# Actuator.net
KiCad netlist of a schematic drawn in EAGLE
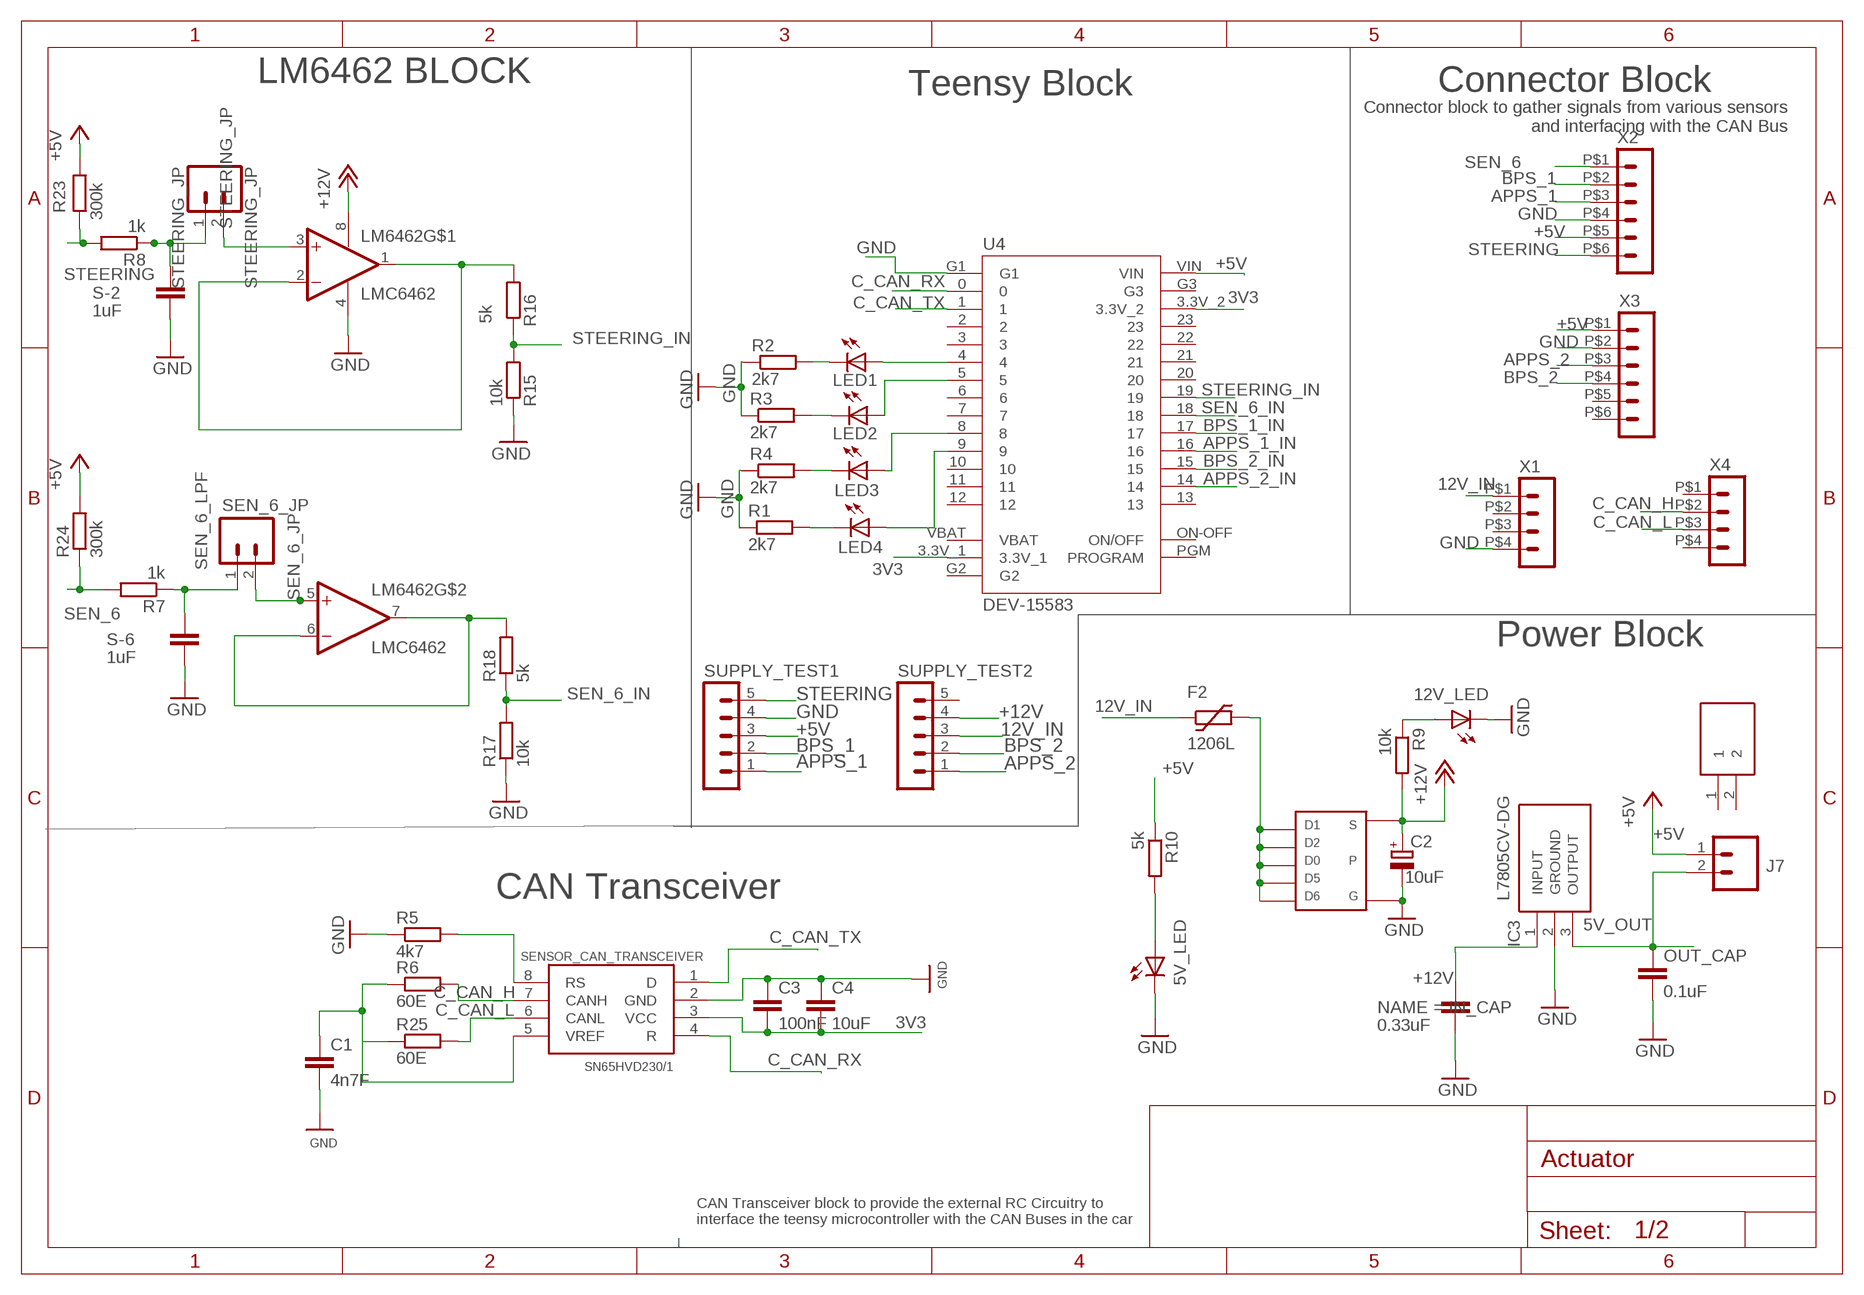
[diagram p0: schematic, sheet 1]
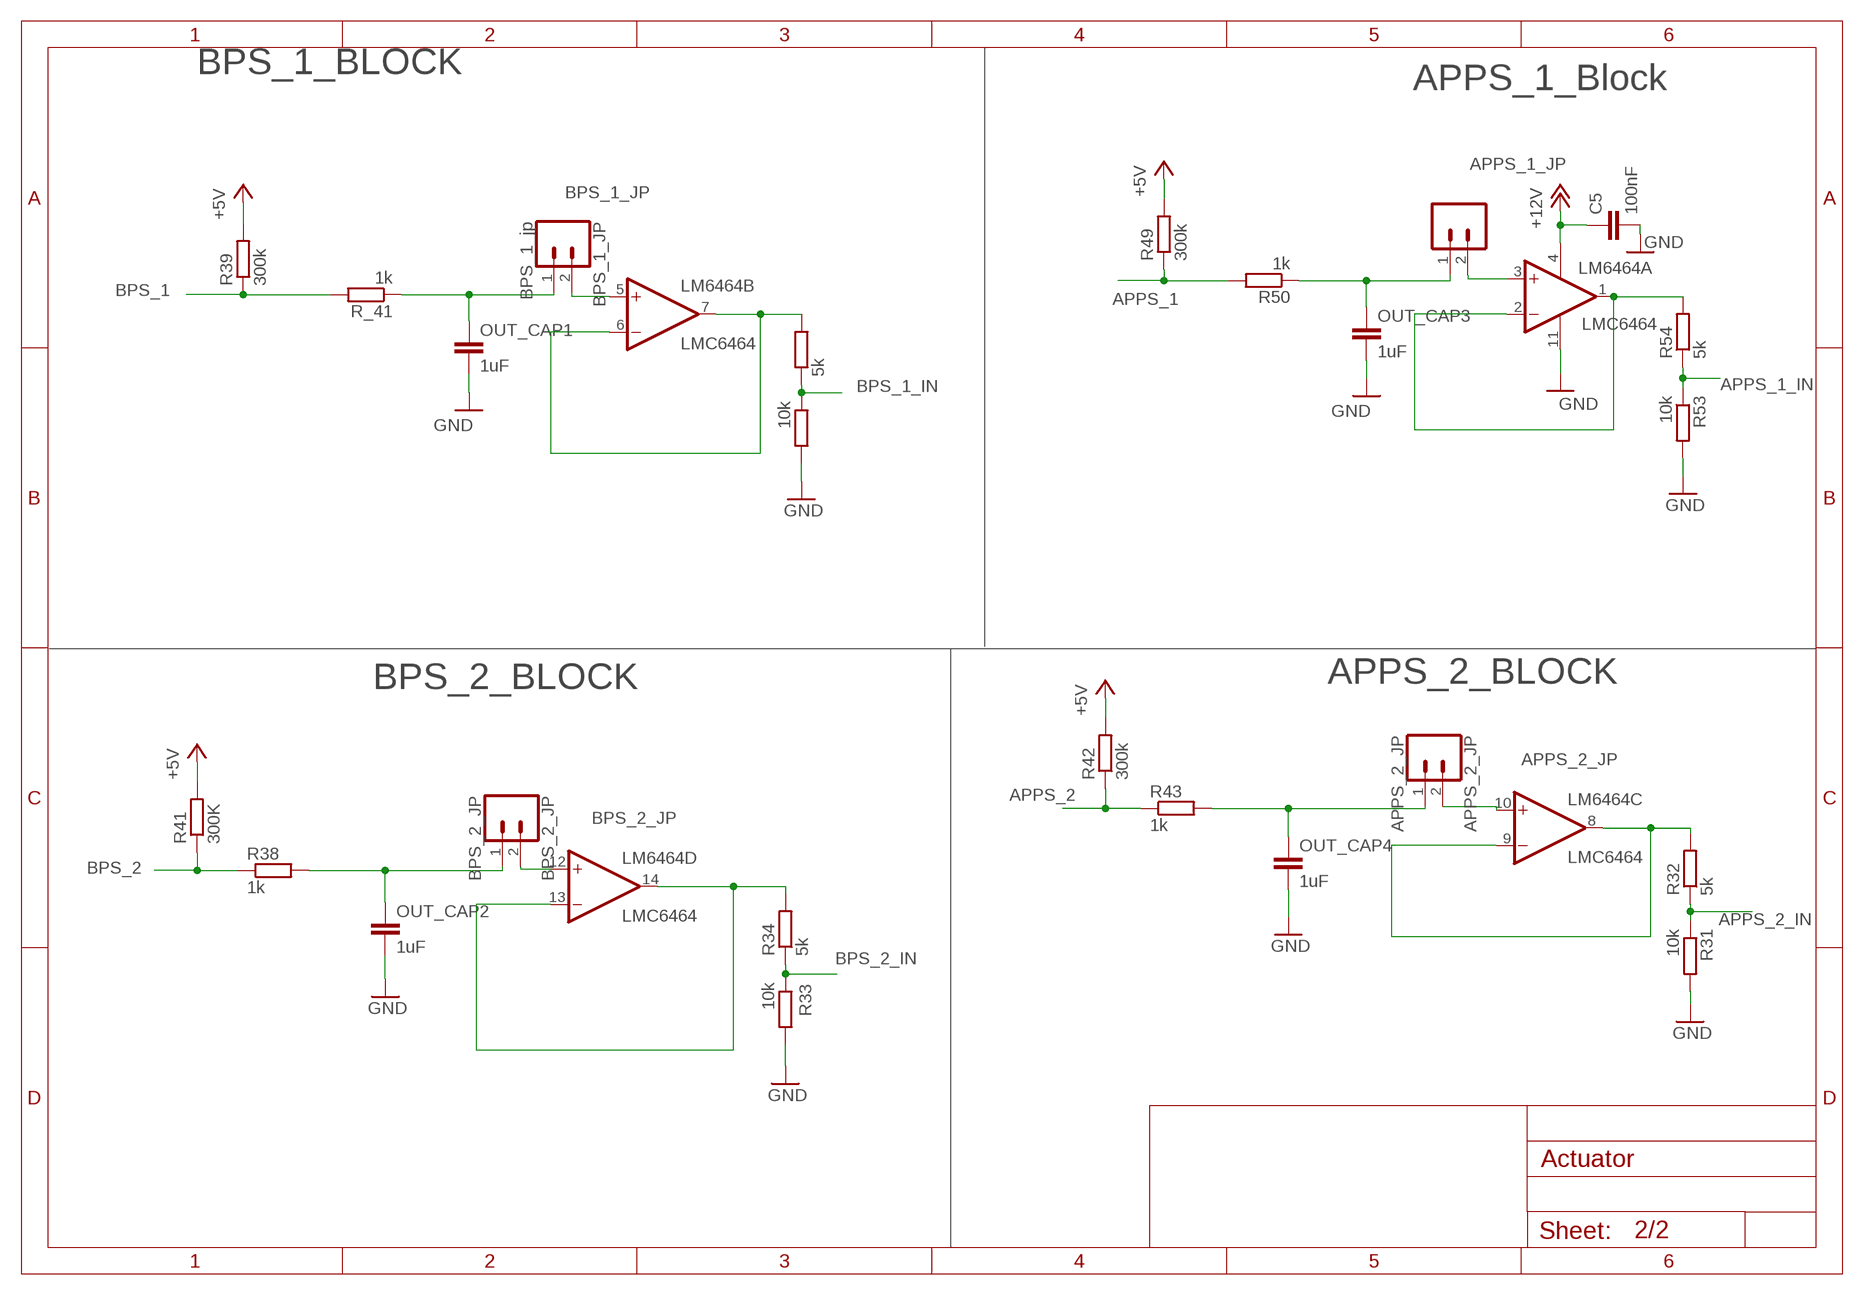
[diagram p1: schematic, sheet 2]

(export (version "E")
  (design (tool "Eeschema 10.0.6"))
  (components
    (comp (ref "5V_LED")
      (value "LED1206")
      (footprint "eagle-import:LED-1206")
      (libsource (lib "eagle-import") (part "LED1206"))
    )
    (comp (ref "12V_LED")
      (value "LED1206")
      (footprint "eagle-import:LED-1206")
      (libsource (lib "eagle-import") (part "LED1206"))
    )
    (comp (ref "C1")
      (value "4n7F")
      (footprint "eagle-import:C0805")
      (libsource (lib "eagle-import") (part "C-EUC0805"))
    )
    (comp (ref "C2")
      (value "10uF")
      (footprint "eagle-import:E2,5-6")
      (libsource (lib "eagle-import") (part "CPOL-EUE2.5-6"))
    )
    (comp (ref "C3")
      (value "100nF")
      (footprint "eagle-import:C0805")
      (libsource (lib "eagle-import") (part "C-EUC0805"))
    )
    (comp (ref "C4")
      (value "10uF")
      (footprint "eagle-import:C0805")
      (libsource (lib "eagle-import") (part "C-EUC0805"))
    )
    (comp (ref "F2")
      (value "1206L")
      (footprint "eagle-import:1206L")
      (libsource (lib "eagle-import") (part "1206L"))
    )
    (comp (ref "IC3")
      (value "L7805CV-DG")
      (footprint "eagle-import:TO255P460X1020X2008-3P")
      (fields (field (name "MOUSER_PART_NUMBER") "511-L7805CV-DG"))
      (libsource (lib "eagle-import") (part "L7805CV-DG"))
    )
    (comp (ref "IN_CAP")
      (value "0.33uF")
      (footprint "eagle-import:C0805")
      (libsource (lib "eagle-import") (part "C-EUC0805"))
    )
    (comp (ref "J7")
      (value "CONN_02")
      (footprint "eagle-import:1X02")
      (libsource (lib "eagle-import") (part "SparkFun-Connectors_CONN_02"))
    )
    (comp (ref "LED1")
      (value "LED1206")
      (footprint "eagle-import:LED-1206")
      (libsource (lib "eagle-import") (part "LED1206"))
    )
    (comp (ref "LED2")
      (value "LED1206")
      (footprint "eagle-import:LED-1206")
      (libsource (lib "eagle-import") (part "LED1206"))
    )
    (comp (ref "LED3")
      (value "LED1206")
      (footprint "eagle-import:LED-1206")
      (libsource (lib "eagle-import") (part "LED1206"))
    )
    (comp (ref "LED4")
      (value "LED1206")
      (footprint "eagle-import:LED-1206")
      (libsource (lib "eagle-import") (part "LED1206"))
    )
    (comp (ref "LM6462")
      (value "LMC6462")
      (footprint "eagle-import:S08")
      (libsource (lib "eagle-import") (part "LMC6462"))
    )
    (comp (ref "OUT_CAP")
      (value "0.1uF")
      (footprint "eagle-import:C0805")
      (libsource (lib "eagle-import") (part "C-EUC0805"))
    )
    (comp (ref "R1")
      (value "2k7")
      (footprint "eagle-import:R0805")
      (libsource (lib "eagle-import") (part "rcl_R-EU_R0805"))
    )
    (comp (ref "R2")
      (value "2k7")
      (footprint "eagle-import:R0805")
      (libsource (lib "eagle-import") (part "rcl_R-EU_R0805"))
    )
    (comp (ref "R3")
      (value "2k7")
      (footprint "eagle-import:R0805")
      (libsource (lib "eagle-import") (part "rcl_R-EU_R0805"))
    )
    (comp (ref "R4")
      (value "2k7")
      (footprint "eagle-import:R0805")
      (libsource (lib "eagle-import") (part "rcl_R-EU_R0805"))
    )
    (comp (ref "R5")
      (value "4k7")
      (footprint "eagle-import:R0805")
      (libsource (lib "eagle-import") (part "R-EU_R0805"))
    )
    (comp (ref "R6")
      (value "60E")
      (footprint "eagle-import:R0805")
      (libsource (lib "eagle-import") (part "R-EU_R0805"))
    )
    (comp (ref "R7")
      (value "1k")
      (footprint "eagle-import:R0805")
      (libsource (lib "eagle-import") (part "IIT_BOMBAY_Racing2_R-EU_R0805"))
    )
    (comp (ref "R8")
      (value "1k")
      (footprint "eagle-import:R0805")
      (libsource (lib "eagle-import") (part "IIT_BOMBAY_Racing2_R-EU_R0805"))
    )
    (comp (ref "R9")
      (value "10k")
      (footprint "eagle-import:R0805")
      (libsource (lib "eagle-import") (part "R-EU_R0805"))
    )
    (comp (ref "R10")
      (value "5k")
      (footprint "eagle-import:R0805")
      (libsource (lib "eagle-import") (part "R-EU_R0805"))
    )
    (comp (ref "R15")
      (value "10k")
      (footprint "eagle-import:R0805")
      (libsource (lib "eagle-import") (part "IIT_BOMBAY_Racing2_R-EU_R0805"))
    )
    (comp (ref "R16")
      (value "5k")
      (footprint "eagle-import:R0805")
      (libsource (lib "eagle-import") (part "IIT_BOMBAY_Racing2_R-EU_R0805"))
    )
    (comp (ref "R17")
      (value "10k")
      (footprint "eagle-import:R0805")
      (libsource (lib "eagle-import") (part "IIT_BOMBAY_Racing2_R-EU_R0805"))
    )
    (comp (ref "R18")
      (value "5k")
      (footprint "eagle-import:R0805")
      (libsource (lib "eagle-import") (part "IIT_BOMBAY_Racing2_R-EU_R0805"))
    )
    (comp (ref "R23")
      (value "300k")
      (footprint "eagle-import:R0805")
      (libsource (lib "eagle-import") (part "IIT_BOMBAY_Racing2_R-EU_R0805"))
    )
    (comp (ref "R24")
      (value "300k")
      (footprint "eagle-import:R0805")
      (libsource (lib "eagle-import") (part "IIT_BOMBAY_Racing2_R-EU_R0805"))
    )
    (comp (ref "R25")
      (value "60E")
      (footprint "eagle-import:R0805")
      (libsource (lib "eagle-import") (part "R-EU_R0805"))
    )
    (comp (ref "S-2")
      (value "1uF")
      (footprint "eagle-import:C0805")
      (libsource (lib "eagle-import") (part "C-EUC0805"))
    )
    (comp (ref "S-6")
      (value "1uF")
      (footprint "eagle-import:C0805")
      (libsource (lib "eagle-import") (part "C-EUC0805"))
    )
    (comp (ref "SENSOR_CAN_TRANSCEIVER")
      (value "SN65HVD230/1")
      (footprint "eagle-import:SO8")
      (libsource (lib "eagle-import") (part "SN65HVD230/1"))
    )
    (comp (ref "SEN_6_JP")
      (value "SEN_6_JP")
      (footprint "eagle-import:1X02")
      (libsource (lib "eagle-import") (part "CONN_02"))
    )
    (comp (ref "STEERING_JP")
      (value "STEERING_JP")
      (footprint "eagle-import:1X02")
      (libsource (lib "eagle-import") (part "CONN_02"))
    )
    (comp (ref "SUPPLY_TEST1")
      (value "MA05-1")
      (footprint "eagle-import:MA05-1")
      (libsource (lib "eagle-import") (part "MA05-1"))
    )
    (comp (ref "SUPPLY_TEST2")
      (value "MA05-1")
      (footprint "eagle-import:MA05-1")
      (libsource (lib "eagle-import") (part "MA05-1"))
    )
    (comp (ref "U$1")
      (value "TSOP-6_PMOS")
      (footprint "eagle-import:TSOP-6_PMOS")
      (libsource (lib "eagle-import") (part "TSOP-6_PMOS"))
    )
    (comp (ref "U3")
      (value "HSS10-B20-P40")
      (footprint "eagle-import:HSS10B20P40")
      (fields (field (name "MOUSER_PART_NUMBER") "490-HSS10-B20-P40"))
      (libsource (lib "eagle-import") (part "HSS10-B20-P40"))
    )
    (comp (ref "U4")
      (value "DEV-15583")
      (footprint "eagle-import:MODULE_DEV-15583")
      (fields (field (name "MF") "SparkFun Electronics"))
      (libsource (lib "eagle-import") (part "DEV-15583"))
    )
    (comp (ref "X1")
      (value "HEADER_POS4_43045-0412")
      (footprint "eagle-import:43045-0412")
      (libsource (lib "eagle-import") (part "HEADER_POS4_?43045-0412"))
    )
    (comp (ref "X2")
      (value "HEADER_POS6_43045-0612")
      (footprint "eagle-import:43045-0612")
      (libsource (lib "eagle-import") (part "HEADER_POS6_?43045-0612"))
    )
    (comp (ref "X3")
      (value "HEADER_POS6_43045-0612")
      (footprint "eagle-import:43045-0612")
      (libsource (lib "eagle-import") (part "HEADER_POS6_?43045-0612"))
    )
    (comp (ref "X4")
      (value "HEADER_POS4_43045-0412")
      (footprint "eagle-import:43045-0412")
      (libsource (lib "eagle-import") (part "HEADER_POS4_?43045-0412"))
    )
    (comp (ref "APPS_1_JP")
      (value "CONN_02")
      (footprint "eagle-import:1X02")
      (libsource (lib "eagle-import") (part "CONN_02"))
    )
    (comp (ref "APPS_2_JP")
      (value "APPS_2_JP")
      (footprint "eagle-import:1X02")
      (libsource (lib "eagle-import") (part "CONN_02"))
    )
    (comp (ref "BPS_1_JP")
      (value "BPS_1_jp")
      (footprint "eagle-import:1X02")
      (libsource (lib "eagle-import") (part "CONN_02"))
    )
    (comp (ref "BPS_2_JP")
      (value "BPS_2_JP")
      (footprint "eagle-import:1X02")
      (libsource (lib "eagle-import") (part "CONN_02"))
    )
    (comp (ref "C5")
      (value "100nF")
      (footprint "eagle-import:C0805")
      (libsource (lib "eagle-import") (part "C-EUC0805"))
    )
    (comp (ref "LM6464")
      (value "LMC6464")
      (footprint "eagle-import:SO14_LONGPADS")
      (libsource (lib "eagle-import") (part "LMC6464"))
    )
    (comp (ref "OUT_CAP1")
      (value "1uF")
      (footprint "eagle-import:C0805")
      (libsource (lib "eagle-import") (part "C-EUC0805"))
    )
    (comp (ref "OUT_CAP2")
      (value "1uF")
      (footprint "eagle-import:C0805")
      (libsource (lib "eagle-import") (part "C-EUC0805"))
    )
    (comp (ref "OUT_CAP3")
      (value "1uF")
      (footprint "eagle-import:C0805")
      (libsource (lib "eagle-import") (part "C-EUC0805"))
    )
    (comp (ref "OUT_CAP4")
      (value "1uF")
      (footprint "eagle-import:C0805")
      (libsource (lib "eagle-import") (part "C-EUC0805"))
    )
    (comp (ref "R29")
      (value "10k")
      (footprint "eagle-import:R0805")
      (libsource (lib "eagle-import") (part "IIT_BOMBAY_Racing2_R-EU_R0805"))
    )
    (comp (ref "R30")
      (value "5k")
      (footprint "eagle-import:R0805")
      (libsource (lib "eagle-import") (part "IIT_BOMBAY_Racing2_R-EU_R0805"))
    )
    (comp (ref "R31")
      (value "10k")
      (footprint "eagle-import:R0805")
      (libsource (lib "eagle-import") (part "IIT_BOMBAY_Racing2_R-EU_R0805"))
    )
    (comp (ref "R32")
      (value "5k")
      (footprint "eagle-import:R0805")
      (libsource (lib "eagle-import") (part "IIT_BOMBAY_Racing2_R-EU_R0805"))
    )
    (comp (ref "R33")
      (value "10k")
      (footprint "eagle-import:R0805")
      (libsource (lib "eagle-import") (part "IIT_BOMBAY_Racing2_R-EU_R0805"))
    )
    (comp (ref "R34")
      (value "5k")
      (footprint "eagle-import:R0805")
      (libsource (lib "eagle-import") (part "IIT_BOMBAY_Racing2_R-EU_R0805"))
    )
    (comp (ref "R38")
      (value "1k")
      (footprint "eagle-import:R0805")
      (libsource (lib "eagle-import") (part "IIT_BOMBAY_Racing2_R-EU_R0805"))
    )
    (comp (ref "R39")
      (value "300k")
      (footprint "eagle-import:R0805")
      (libsource (lib "eagle-import") (part "IIT_BOMBAY_Racing2_R-EU_R0805"))
    )
    (comp (ref "R41")
      (value "300K")
      (footprint "eagle-import:R0805")
      (libsource (lib "eagle-import") (part "IIT_BOMBAY_Racing2_R-EU_R0805"))
    )
    (comp (ref "R42")
      (value "300k")
      (footprint "eagle-import:R0805")
      (libsource (lib "eagle-import") (part "IIT_BOMBAY_Racing2_R-EU_R0805"))
    )
    (comp (ref "R43")
      (value "1k")
      (footprint "eagle-import:R0805")
      (libsource (lib "eagle-import") (part "IIT_BOMBAY_Racing2_R-EU_R0805"))
    )
    (comp (ref "R49")
      (value "300k")
      (footprint "eagle-import:R0805")
      (libsource (lib "eagle-import") (part "IIT_BOMBAY_Racing2_R-EU_R0805"))
    )
    (comp (ref "R50")
      (value "1k")
      (footprint "eagle-import:R0805")
      (libsource (lib "eagle-import") (part "IIT_BOMBAY_Racing2_R-EU_R0805"))
    )
    (comp (ref "R53")
      (value "10k")
      (footprint "eagle-import:R0805")
      (libsource (lib "eagle-import") (part "IIT_BOMBAY_Racing2_R-EU_R0805"))
    )
    (comp (ref "R54")
      (value "5k")
      (footprint "eagle-import:R0805")
      (libsource (lib "eagle-import") (part "IIT_BOMBAY_Racing2_R-EU_R0805"))
    )
    (comp (ref "R_41")
      (value "1k")
      (footprint "eagle-import:R0805")
      (libsource (lib "eagle-import") (part "IIT_BOMBAY_Racing2_R-EU_R0805"))
    )
  )
  (nets
    (net (code "1") (name "+5V") (class "Default")
      (node (ref "J7") (pin "1") (pinfunction "1_1") (pintype "passive"))
      (node (ref "R10") (pin "1") (pinfunction "1_1") (pintype "passive"))
      (node (ref "R23") (pin "2") (pinfunction "2_2") (pintype "passive"))
      (node (ref "R24") (pin "2") (pinfunction "2_2") (pintype "passive"))
      (node (ref "R39") (pin "2") (pinfunction "2_2") (pintype "passive"))
      (node (ref "R41") (pin "2") (pinfunction "2_2") (pintype "passive"))
      (node (ref "R42") (pin "2") (pinfunction "2_2") (pintype "passive"))
      (node (ref "R49") (pin "2") (pinfunction "2_2") (pintype "passive"))
      (node (ref "SUPPLY_TEST1") (pin "3") (pinfunction "3_3") (pintype "passive"))
      (node (ref "U4") (pin "VIN") (pinfunction "VIN_VIN") (pintype "power_in"))
      (node (ref "X2") (pin "P$5") (pinfunction "5_P$5") (pintype "passive"))
      (node (ref "X3") (pin "P$1") (pinfunction "1_P$1") (pintype "passive"))
    )
    (net (code "2") (name "+12V") (class "Default")
      (node (ref "C2") (pin "+") (pinfunction "+_+") (pintype "passive"))
      (node (ref "C5") (pin "1") (pinfunction "1_1") (pintype "passive"))
      (node (ref "IC3") (pin "1") (pinfunction "INPUT_1") (pintype "bidirectional"))
      (node (ref "IN_CAP") (pin "1") (pinfunction "1_1") (pintype "passive"))
      (node (ref "LM6462") (pin "8") (pinfunction "V+_8") (pintype "power_in"))
      (node (ref "LM6464") (pin "4") (pinfunction "V+_4") (pintype "power_in"))
      (node (ref "R9") (pin "2") (pinfunction "2_2") (pintype "passive"))
      (node (ref "SUPPLY_TEST2") (pin "4") (pinfunction "4_4") (pintype "passive"))
      (node (ref "U$1") (pin "S") (pinfunction "S_S") (pintype "bidirectional"))
    )
    (net (code "3") (name "3V3") (class "Default")
      (node (ref "C3") (pin "2") (pinfunction "2_2") (pintype "passive"))
      (node (ref "C4") (pin "2") (pinfunction "2_2") (pintype "passive"))
      (node (ref "SENSOR_CAN_TRANSCEIVER") (pin "3") (pinfunction "VCC_3") (pintype "power_in"))
      (node (ref "U4") (pin "3.3V_1") (pinfunction "3.3V_1_3.3V_1") (pintype "power_in"))
      (node (ref "U4") (pin "3.3V_2") (pinfunction "3.3V_2_3.3V_2") (pintype "power_in"))
    )
    (net (code "4") (name "5V_OUT") (class "Default")
      (node (ref "IC3") (pin "3") (pinfunction "OUTPUT_3") (pintype "bidirectional"))
      (node (ref "J7") (pin "2") (pinfunction "2_2") (pintype "passive"))
      (node (ref "OUT_CAP") (pin "1") (pinfunction "1_1") (pintype "passive"))
    )
    (net (code "5") (name "12V_IN") (class "Default")
      (node (ref "F2") (pin "P$1") (pinfunction "1_P$1") (pintype "passive"))
      (node (ref "SUPPLY_TEST2") (pin "3") (pinfunction "3_3") (pintype "passive"))
      (node (ref "X1") (pin "P$1") (pinfunction "1_P$1") (pintype "passive"))
    )
    (net (code "6") (name "APPS_1") (class "Default")
      (node (ref "R49") (pin "1") (pinfunction "1_1") (pintype "passive"))
      (node (ref "R50") (pin "2") (pinfunction "2_2") (pintype "passive"))
      (node (ref "SUPPLY_TEST1") (pin "1") (pinfunction "1_1") (pintype "passive"))
      (node (ref "X2") (pin "P$3") (pinfunction "3_P$3") (pintype "passive"))
    )
    (net (code "7") (name "APPS_1_IN") (class "Default")
      (node (ref "R53") (pin "1") (pinfunction "1_1") (pintype "passive"))
      (node (ref "R54") (pin "1") (pinfunction "1_1") (pintype "passive"))
      (node (ref "U4") (pin "16") (pinfunction "16_16") (pintype "bidirectional"))
    )
    (net (code "8") (name "APPS_1_JP") (class "Default")
      (node (ref "APPS_1_JP") (pin "2") (pinfunction "2_2") (pintype "passive"))
      (node (ref "LM6464") (pin "3") (pinfunction "+IN_3") (pintype "input"))
    )
    (net (code "9") (name "APPS_2") (class "Default")
      (node (ref "R42") (pin "1") (pinfunction "1_1") (pintype "passive"))
      (node (ref "R43") (pin "1") (pinfunction "1_1") (pintype "passive"))
      (node (ref "SUPPLY_TEST2") (pin "1") (pinfunction "1_1") (pintype "passive"))
      (node (ref "X3") (pin "P$3") (pinfunction "3_P$3") (pintype "passive"))
    )
    (net (code "10") (name "APPS_2_IN") (class "Default")
      (node (ref "R31") (pin "1") (pinfunction "1_1") (pintype "passive"))
      (node (ref "R32") (pin "1") (pinfunction "1_1") (pintype "passive"))
      (node (ref "U4") (pin "14") (pinfunction "14_14") (pintype "bidirectional"))
    )
    (net (code "11") (name "APPS_2_JP") (class "Default")
      (node (ref "APPS_2_JP") (pin "2") (pinfunction "2_2") (pintype "passive"))
      (node (ref "LM6464") (pin "10") (pinfunction "+IN_10") (pintype "input"))
    )
    (net (code "12") (name "BPS_1") (class "Default")
      (node (ref "R39") (pin "1") (pinfunction "1_1") (pintype "passive"))
      (node (ref "R_41") (pin "2") (pinfunction "2_2") (pintype "passive"))
      (node (ref "SUPPLY_TEST1") (pin "2") (pinfunction "2_2") (pintype "passive"))
      (node (ref "X2") (pin "P$2") (pinfunction "2_P$2") (pintype "passive"))
    )
    (net (code "13") (name "BPS_1_IN") (class "Default")
      (node (ref "R29") (pin "1") (pinfunction "1_1") (pintype "passive"))
      (node (ref "R30") (pin "1") (pinfunction "1_1") (pintype "passive"))
      (node (ref "U4") (pin "17") (pinfunction "17_17") (pintype "bidirectional"))
    )
    (net (code "14") (name "BPS_1_JP") (class "Default")
      (node (ref "BPS_1_JP") (pin "2") (pinfunction "2_2") (pintype "passive"))
      (node (ref "LM6464") (pin "5") (pinfunction "+IN_5") (pintype "input"))
    )
    (net (code "15") (name "BPS_2") (class "Default")
      (node (ref "R38") (pin "1") (pinfunction "1_1") (pintype "passive"))
      (node (ref "R41") (pin "1") (pinfunction "1_1") (pintype "passive"))
      (node (ref "SUPPLY_TEST2") (pin "2") (pinfunction "2_2") (pintype "passive"))
      (node (ref "X3") (pin "P$4") (pinfunction "4_P$4") (pintype "passive"))
    )
    (net (code "16") (name "BPS_2_IN") (class "Default")
      (node (ref "R33") (pin "1") (pinfunction "1_1") (pintype "passive"))
      (node (ref "R34") (pin "1") (pinfunction "1_1") (pintype "passive"))
      (node (ref "U4") (pin "15") (pinfunction "15_15") (pintype "bidirectional"))
    )
    (net (code "17") (name "BPS_2_JP") (class "Default")
      (node (ref "BPS_2_JP") (pin "2") (pinfunction "2_2") (pintype "passive"))
      (node (ref "LM6464") (pin "12") (pinfunction "+IN_12") (pintype "input"))
    )
    (net (code "18") (name "C_CAN_H") (class "Default")
      (node (ref "R6") (pin "2") (pinfunction "2_2") (pintype "passive"))
      (node (ref "SENSOR_CAN_TRANSCEIVER") (pin "7") (pinfunction "CANH_7") (pintype "bidirectional"))
      (node (ref "X4") (pin "P$2") (pinfunction "2_P$2") (pintype "passive"))
    )
    (net (code "19") (name "C_CAN_L") (class "Default")
      (node (ref "R25") (pin "2") (pinfunction "2_2") (pintype "passive"))
      (node (ref "SENSOR_CAN_TRANSCEIVER") (pin "6") (pinfunction "CANL_6") (pintype "bidirectional"))
      (node (ref "X4") (pin "P$3") (pinfunction "3_P$3") (pintype "passive"))
    )
    (net (code "20") (name "C_CAN_RX") (class "Default")
      (node (ref "SENSOR_CAN_TRANSCEIVER") (pin "4") (pinfunction "R_4") (pintype "bidirectional"))
      (node (ref "U4") (pin "0") (pinfunction "0_0") (pintype "bidirectional"))
    )
    (net (code "21") (name "C_CAN_TX") (class "Default")
      (node (ref "SENSOR_CAN_TRANSCEIVER") (pin "1") (pinfunction "D_1") (pintype "bidirectional"))
      (node (ref "U4") (pin "1") (pinfunction "1_1") (pintype "bidirectional"))
    )
    (net (code "22") (name "G2") (class "Default")
      (node (ref "U4") (pin "G2") (pinfunction "G2_G2") (pintype "power_in"))
    )
    (net (code "23") (name "G3") (class "Default")
      (node (ref "U4") (pin "G3") (pinfunction "G3_G3") (pintype "power_in"))
    )
    (net (code "24") (name "GND") (class "Default")
      (node (ref "12V_LED") (pin "C") (pinfunction "C_C") (pintype "passive"))
      (node (ref "5V_LED") (pin "C") (pinfunction "C_C") (pintype "passive"))
      (node (ref "C1") (pin "2") (pinfunction "2_2") (pintype "passive"))
      (node (ref "C2") (pin "-") (pinfunction "-_-") (pintype "passive"))
      (node (ref "C3") (pin "1") (pinfunction "1_1") (pintype "passive"))
      (node (ref "C4") (pin "1") (pinfunction "1_1") (pintype "passive"))
      (node (ref "C5") (pin "2") (pinfunction "2_2") (pintype "passive"))
      (node (ref "IC3") (pin "2") (pinfunction "GROUND_2") (pintype "bidirectional"))
      (node (ref "IN_CAP") (pin "2") (pinfunction "2_2") (pintype "passive"))
      (node (ref "LM6462") (pin "4") (pinfunction "V-_4") (pintype "power_in"))
      (node (ref "LM6464") (pin "11") (pinfunction "V-_11") (pintype "power_in"))
      (node (ref "OUT_CAP") (pin "2") (pinfunction "2_2") (pintype "passive"))
      (node (ref "OUT_CAP1") (pin "2") (pinfunction "2_2") (pintype "passive"))
      (node (ref "OUT_CAP2") (pin "2") (pinfunction "2_2") (pintype "passive"))
      (node (ref "OUT_CAP3") (pin "2") (pinfunction "2_2") (pintype "passive"))
      (node (ref "OUT_CAP4") (pin "2") (pinfunction "2_2") (pintype "passive"))
      (node (ref "R1") (pin "1") (pinfunction "1_1") (pintype "passive"))
      (node (ref "R15") (pin "1") (pinfunction "1_1") (pintype "passive"))
      (node (ref "R17") (pin "1") (pinfunction "1_1") (pintype "passive"))
      (node (ref "R2") (pin "1") (pinfunction "1_1") (pintype "passive"))
      (node (ref "R29") (pin "2") (pinfunction "2_2") (pintype "passive"))
      (node (ref "R3") (pin "1") (pinfunction "1_1") (pintype "passive"))
      (node (ref "R31") (pin "2") (pinfunction "2_2") (pintype "passive"))
      (node (ref "R33") (pin "2") (pinfunction "2_2") (pintype "passive"))
      (node (ref "R4") (pin "1") (pinfunction "1_1") (pintype "passive"))
      (node (ref "R5") (pin "1") (pinfunction "1_1") (pintype "passive"))
      (node (ref "R53") (pin "2") (pinfunction "2_2") (pintype "passive"))
      (node (ref "S-2") (pin "2") (pinfunction "2_2") (pintype "passive"))
      (node (ref "S-6") (pin "2") (pinfunction "2_2") (pintype "passive"))
      (node (ref "SENSOR_CAN_TRANSCEIVER") (pin "2") (pinfunction "GND_2") (pintype "power_in"))
      (node (ref "SUPPLY_TEST1") (pin "4") (pinfunction "4_4") (pintype "passive"))
      (node (ref "U$1") (pin "G") (pinfunction "G_G") (pintype "bidirectional"))
      (node (ref "U4") (pin "G1") (pinfunction "G1_G1") (pintype "power_in"))
      (node (ref "X1") (pin "P$4") (pinfunction "4_P$4") (pintype "passive"))
      (node (ref "X2") (pin "P$4") (pinfunction "4_P$4") (pintype "passive"))
      (node (ref "X3") (pin "P$2") (pinfunction "2_P$2") (pintype "passive"))
    )
    (net (code "25") (name "Net-(5V_LED-PadA)") (class "Default")
      (node (ref "5V_LED") (pin "A") (pinfunction "A_A") (pintype "passive"))
      (node (ref "R10") (pin "2") (pinfunction "2_2") (pintype "passive"))
    )
    (net (code "26") (name "Net-(12V_LED-PadA)") (class "Default")
      (node (ref "12V_LED") (pin "A") (pinfunction "A_A") (pintype "passive"))
      (node (ref "R9") (pin "1") (pinfunction "1_1") (pintype "passive"))
    )
    (net (code "27") (name "Net-(APPS_1_JP-Pad1)") (class "Default")
      (node (ref "APPS_1_JP") (pin "1") (pinfunction "1_1") (pintype "passive"))
      (node (ref "OUT_CAP3") (pin "1") (pinfunction "1_1") (pintype "passive"))
      (node (ref "R50") (pin "1") (pinfunction "1_1") (pintype "passive"))
    )
    (net (code "28") (name "Net-(APPS_2_JP-Pad1)") (class "Default")
      (node (ref "APPS_2_JP") (pin "1") (pinfunction "1_1") (pintype "passive"))
      (node (ref "OUT_CAP4") (pin "1") (pinfunction "1_1") (pintype "passive"))
      (node (ref "R43") (pin "2") (pinfunction "2_2") (pintype "passive"))
    )
    (net (code "29") (name "Net-(BPS_1_JP-Pad1)") (class "Default")
      (node (ref "BPS_1_JP") (pin "1") (pinfunction "1_1") (pintype "passive"))
      (node (ref "OUT_CAP1") (pin "1") (pinfunction "1_1") (pintype "passive"))
      (node (ref "R_41") (pin "1") (pinfunction "1_1") (pintype "passive"))
    )
    (net (code "30") (name "Net-(BPS_2_JP-Pad1)") (class "Default")
      (node (ref "BPS_2_JP") (pin "1") (pinfunction "1_1") (pintype "passive"))
      (node (ref "OUT_CAP2") (pin "1") (pinfunction "1_1") (pintype "passive"))
      (node (ref "R38") (pin "2") (pinfunction "2_2") (pintype "passive"))
    )
    (net (code "31") (name "Net-(F2-2)") (class "Default")
      (node (ref "F2") (pin "P$2") (pinfunction "2_P$2") (pintype "passive"))
      (node (ref "U$1") (pin "1") (pinfunction "1_1") (pintype "bidirectional"))
      (node (ref "U$1") (pin "2") (pinfunction "2_2") (pintype "bidirectional"))
      (node (ref "U$1") (pin "5") (pinfunction "5_5") (pintype "bidirectional"))
      (node (ref "U$1") (pin "6") (pinfunction "6_6") (pintype "bidirectional"))
      (node (ref "U$1") (pin "D") (pinfunction "D0_D") (pintype "bidirectional"))
    )
    (net (code "32") (name "Net-(LED1-PadA)") (class "Default")
      (node (ref "LED1") (pin "A") (pinfunction "A_A") (pintype "passive"))
      (node (ref "U4") (pin "4") (pinfunction "4_4") (pintype "bidirectional"))
    )
    (net (code "33") (name "Net-(LED1-PadC)") (class "Default")
      (node (ref "LED1") (pin "C") (pinfunction "C_C") (pintype "passive"))
      (node (ref "R2") (pin "2") (pinfunction "2_2") (pintype "passive"))
    )
    (net (code "34") (name "Net-(LED2-PadA)") (class "Default")
      (node (ref "LED2") (pin "A") (pinfunction "A_A") (pintype "passive"))
      (node (ref "U4") (pin "5") (pinfunction "5_5") (pintype "bidirectional"))
    )
    (net (code "35") (name "Net-(LED2-PadC)") (class "Default")
      (node (ref "LED2") (pin "C") (pinfunction "C_C") (pintype "passive"))
      (node (ref "R3") (pin "2") (pinfunction "2_2") (pintype "passive"))
    )
    (net (code "36") (name "Net-(LED3-PadA)") (class "Default")
      (node (ref "LED3") (pin "A") (pinfunction "A_A") (pintype "passive"))
      (node (ref "U4") (pin "8") (pinfunction "8_8") (pintype "bidirectional"))
    )
    (net (code "37") (name "Net-(LED3-PadC)") (class "Default")
      (node (ref "LED3") (pin "C") (pinfunction "C_C") (pintype "passive"))
      (node (ref "R4") (pin "2") (pinfunction "2_2") (pintype "passive"))
    )
    (net (code "38") (name "Net-(LED4-PadA)") (class "Default")
      (node (ref "LED4") (pin "A") (pinfunction "A_A") (pintype "passive"))
      (node (ref "U4") (pin "9") (pinfunction "9_9") (pintype "bidirectional"))
    )
    (net (code "39") (name "Net-(LED4-PadC)") (class "Default")
      (node (ref "LED4") (pin "C") (pinfunction "C_C") (pintype "passive"))
      (node (ref "R1") (pin "2") (pinfunction "2_2") (pintype "passive"))
    )
    (net (code "40") (name "Net-(LM6462A--IN)") (class "Default")
      (node (ref "LM6462") (pin "1") (pinfunction "OUT_1") (pintype "output"))
      (node (ref "LM6462") (pin "2") (pinfunction "-IN_2") (pintype "input"))
      (node (ref "R16") (pin "2") (pinfunction "2_2") (pintype "passive"))
    )
    (net (code "41") (name "Net-(LM6462B--IN)") (class "Default")
      (node (ref "LM6462") (pin "6") (pinfunction "-IN_6") (pintype "input"))
      (node (ref "LM6462") (pin "7") (pinfunction "OUT_7") (pintype "output"))
      (node (ref "R18") (pin "2") (pinfunction "2_2") (pintype "passive"))
    )
    (net (code "42") (name "Net-(LM6464A--IN)") (class "Default")
      (node (ref "LM6464") (pin "1") (pinfunction "OUT_1") (pintype "output"))
      (node (ref "LM6464") (pin "2") (pinfunction "-IN_2") (pintype "input"))
      (node (ref "R54") (pin "2") (pinfunction "2_2") (pintype "passive"))
    )
    (net (code "43") (name "Net-(LM6464B--IN)") (class "Default")
      (node (ref "LM6464") (pin "6") (pinfunction "-IN_6") (pintype "input"))
      (node (ref "LM6464") (pin "7") (pinfunction "OUT_7") (pintype "output"))
      (node (ref "R30") (pin "2") (pinfunction "2_2") (pintype "passive"))
    )
    (net (code "44") (name "Net-(LM6464C--IN)") (class "Default")
      (node (ref "LM6464") (pin "8") (pinfunction "OUT_8") (pintype "output"))
      (node (ref "LM6464") (pin "9") (pinfunction "-IN_9") (pintype "input"))
      (node (ref "R32") (pin "2") (pinfunction "2_2") (pintype "passive"))
    )
    (net (code "45") (name "Net-(LM6464D--IN)") (class "Default")
      (node (ref "LM6464") (pin "13") (pinfunction "-IN_13") (pintype "input"))
      (node (ref "LM6464") (pin "14") (pinfunction "OUT_14") (pintype "output"))
      (node (ref "R34") (pin "2") (pinfunction "2_2") (pintype "passive"))
    )
    (net (code "46") (name "Net-(R8-Pad1)") (class "Default")
      (node (ref "R8") (pin "1") (pinfunction "1_1") (pintype "passive"))
      (node (ref "S-2") (pin "1") (pinfunction "1_1") (pintype "passive"))
      (node (ref "STEERING_JP") (pin "1") (pinfunction "1_1") (pintype "passive"))
    )
    (net (code "47") (name "Net-(SENSOR_CAN_TRANSCEIVER-RS)") (class "Default")
      (node (ref "R5") (pin "2") (pinfunction "2_2") (pintype "passive"))
      (node (ref "SENSOR_CAN_TRANSCEIVER") (pin "8") (pinfunction "RS_8") (pintype "bidirectional"))
    )
    (net (code "48") (name "Net-(SENSOR_CAN_TRANSCEIVER-VREF)") (class "Default")
      (node (ref "C1") (pin "1") (pinfunction "1_1") (pintype "passive"))
      (node (ref "R25") (pin "1") (pinfunction "1_1") (pintype "passive"))
      (node (ref "R6") (pin "1") (pinfunction "1_1") (pintype "passive"))
      (node (ref "SENSOR_CAN_TRANSCEIVER") (pin "5") (pinfunction "VREF_5") (pintype "bidirectional"))
    )
    (net (code "49") (name "SEN_6") (class "Default")
      (node (ref "R24") (pin "1") (pinfunction "1_1") (pintype "passive"))
      (node (ref "R7") (pin "2") (pinfunction "2_2") (pintype "passive"))
      (node (ref "X2") (pin "P$1") (pinfunction "1_P$1") (pintype "passive"))
    )
    (net (code "50") (name "SEN_6_IN") (class "Default")
      (node (ref "R17") (pin "2") (pinfunction "2_2") (pintype "passive"))
      (node (ref "R18") (pin "1") (pinfunction "1_1") (pintype "passive"))
      (node (ref "U4") (pin "18") (pinfunction "18_18") (pintype "bidirectional"))
    )
    (net (code "51") (name "SEN_6_JP") (class "Default")
      (node (ref "LM6462") (pin "5") (pinfunction "+IN_5") (pintype "input"))
      (node (ref "SEN_6_JP") (pin "2") (pinfunction "2_2") (pintype "passive"))
    )
    (net (code "52") (name "SEN_6_LPF") (class "Default")
      (node (ref "R7") (pin "1") (pinfunction "1_1") (pintype "passive"))
      (node (ref "S-6") (pin "1") (pinfunction "1_1") (pintype "passive"))
      (node (ref "SEN_6_JP") (pin "1") (pinfunction "1_1") (pintype "passive"))
    )
    (net (code "53") (name "STEERING") (class "Default")
      (node (ref "R23") (pin "1") (pinfunction "1_1") (pintype "passive"))
      (node (ref "R8") (pin "2") (pinfunction "2_2") (pintype "passive"))
      (node (ref "SUPPLY_TEST1") (pin "5") (pinfunction "5_5") (pintype "passive"))
      (node (ref "X2") (pin "P$6") (pinfunction "6_P$6") (pintype "passive"))
    )
    (net (code "54") (name "STEERING_IN") (class "Default")
      (node (ref "R15") (pin "2") (pinfunction "2_2") (pintype "passive"))
      (node (ref "R16") (pin "1") (pinfunction "1_1") (pintype "passive"))
      (node (ref "U4") (pin "19") (pinfunction "19_19") (pintype "bidirectional"))
    )
    (net (code "55") (name "STEERING_JP") (class "Default")
      (node (ref "LM6462") (pin "3") (pinfunction "+IN_3") (pintype "input"))
      (node (ref "STEERING_JP") (pin "2") (pinfunction "2_2") (pintype "passive"))
    )
    (net (code "56") (name "VBAT") (class "Default")
      (node (ref "U4") (pin "VBAT") (pinfunction "VBAT_VBAT") (pintype "power_in"))
    )
    (net (code "57") (name "unconnected-(SUPPLY_TEST2-Pad5)") (class "Default")
      (node (ref "SUPPLY_TEST2") (pin "5") (pinfunction "5_5") (pintype "passive"))
    )
    (net (code "58") (name "unconnected-(U3-Pad1)") (class "Default")
      (node (ref "U3") (pin "1") (pinfunction "1_1") (pintype "bidirectional"))
    )
    (net (code "59") (name "unconnected-(U3-Pad2)") (class "Default")
      (node (ref "U3") (pin "2") (pinfunction "2_2") (pintype "bidirectional"))
    )
    (net (code "60") (name "unconnected-(U4-ON{slash}OFF-PadON-OFF)") (class "Default")
      (node (ref "U4") (pin "ON-OFF") (pinfunction "ON/OFF_ON-OFF") (pintype "bidirectional"))
    )
    (net (code "61") (name "unconnected-(U4-PROGRAM-PadPGM)") (class "Default")
      (node (ref "U4") (pin "PGM") (pinfunction "PROGRAM_PGM") (pintype "bidirectional"))
    )
    (net (code "62") (name "unconnected-(U4-Pad2)") (class "Default")
      (node (ref "U4") (pin "2") (pinfunction "2_2") (pintype "bidirectional"))
    )
    (net (code "63") (name "unconnected-(U4-Pad3)") (class "Default")
      (node (ref "U4") (pin "3") (pinfunction "3_3") (pintype "bidirectional"))
    )
    (net (code "64") (name "unconnected-(U4-Pad6)") (class "Default")
      (node (ref "U4") (pin "6") (pinfunction "6_6") (pintype "bidirectional"))
    )
    (net (code "65") (name "unconnected-(U4-Pad7)") (class "Default")
      (node (ref "U4") (pin "7") (pinfunction "7_7") (pintype "bidirectional"))
    )
    (net (code "66") (name "unconnected-(U4-Pad10)") (class "Default")
      (node (ref "U4") (pin "10") (pinfunction "10_10") (pintype "bidirectional"))
    )
    (net (code "67") (name "unconnected-(U4-Pad11)") (class "Default")
      (node (ref "U4") (pin "11") (pinfunction "11_11") (pintype "bidirectional"))
    )
    (net (code "68") (name "unconnected-(U4-Pad12)") (class "Default")
      (node (ref "U4") (pin "12") (pinfunction "12_12") (pintype "bidirectional"))
    )
    (net (code "69") (name "unconnected-(U4-Pad13)") (class "Default")
      (node (ref "U4") (pin "13") (pinfunction "13_13") (pintype "bidirectional"))
    )
    (net (code "70") (name "unconnected-(U4-Pad20)") (class "Default")
      (node (ref "U4") (pin "20") (pinfunction "20_20") (pintype "bidirectional"))
    )
    (net (code "71") (name "unconnected-(U4-Pad21)") (class "Default")
      (node (ref "U4") (pin "21") (pinfunction "21_21") (pintype "bidirectional"))
    )
    (net (code "72") (name "unconnected-(U4-Pad22)") (class "Default")
      (node (ref "U4") (pin "22") (pinfunction "22_22") (pintype "bidirectional"))
    )
    (net (code "73") (name "unconnected-(U4-Pad23)") (class "Default")
      (node (ref "U4") (pin "23") (pinfunction "23_23") (pintype "bidirectional"))
    )
    (net (code "74") (name "unconnected-(X1-2-PadP$2)") (class "Default")
      (node (ref "X1") (pin "P$2") (pinfunction "2_P$2") (pintype "passive"))
    )
    (net (code "75") (name "unconnected-(X1-3-PadP$3)") (class "Default")
      (node (ref "X1") (pin "P$3") (pinfunction "3_P$3") (pintype "passive"))
    )
    (net (code "76") (name "unconnected-(X3-5-PadP$5)") (class "Default")
      (node (ref "X3") (pin "P$5") (pinfunction "5_P$5") (pintype "passive"))
    )
    (net (code "77") (name "unconnected-(X3-6-PadP$6)") (class "Default")
      (node (ref "X3") (pin "P$6") (pinfunction "6_P$6") (pintype "passive"))
    )
    (net (code "78") (name "unconnected-(X4-1-PadP$1)") (class "Default")
      (node (ref "X4") (pin "P$1") (pinfunction "1_P$1") (pintype "passive"))
    )
    (net (code "79") (name "unconnected-(X4-4-PadP$4)") (class "Default")
      (node (ref "X4") (pin "P$4") (pinfunction "4_P$4") (pintype "passive"))
    )
  )
)
